# SwitchMultiControl.net
KiCad netlist of a schematic drawn in Altium Designer
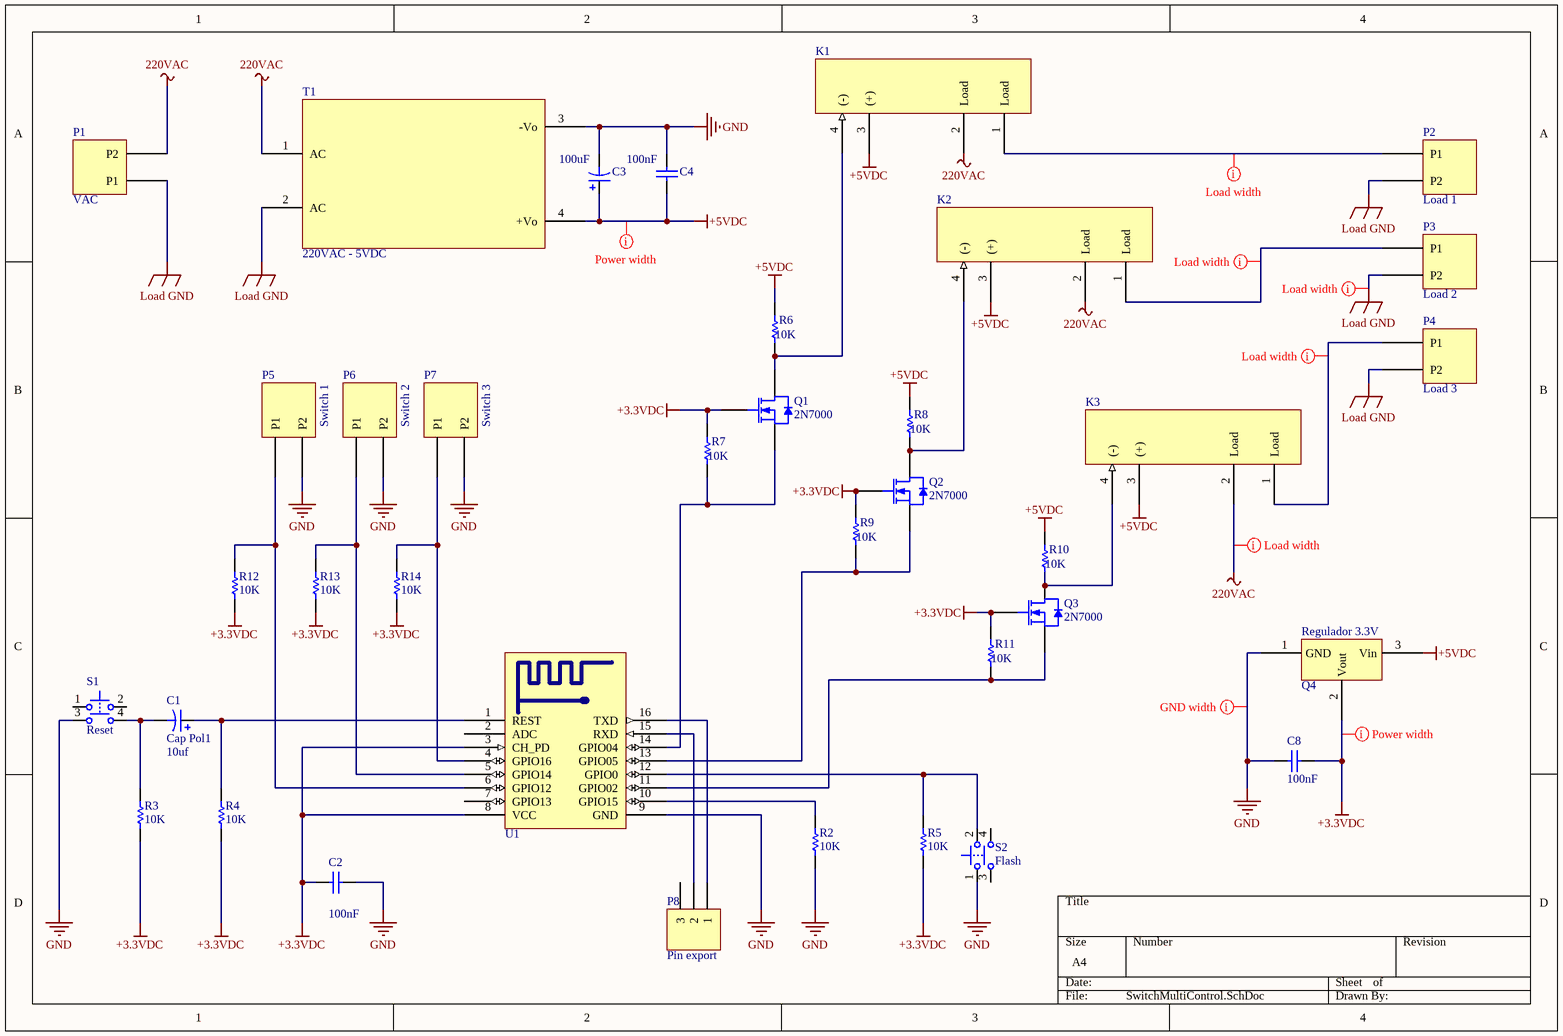
[diagram p0: SwitchMultiControl.SchDoc]

(export (version "E")
  (design (tool "Eeschema 10.0.6"))
  (components
    (comp (ref "C1")
      (value "Cap Pol1")
      (footprint "RAD-0.1")
      (description "Polarized Capacitor (Radial)")
      (fields (field (name "ALTIUM_VALUE") "10uf") (field (name "PUBLISHER") "Altium Limited"))
      (libsource (lib "Miscellaneous Devices") (part "Cap Pol1"))
    )
    (comp (ref "C2")
      (value "100nF")
      (footprint "RAD-0.1")
      (description "Capacitor")
      (fields (field (name "Comment") "Cap") (field (name "PUBLISHER") "Altium Limited"))
      (libsource (lib "Miscellaneous Devices") (part "Cap"))
    )
    (comp (ref "C3")
      (value "100uF")
      (footprint "RAD-0.1")
      (description "Polarized Capacitor (Radial)")
      (fields (field (name "Comment") "Cap Pol1") (field (name "PUBLISHER") "Altium Limited"))
      (libsource (lib "Miscellaneous Devices") (part "Cap Pol1"))
    )
    (comp (ref "C4")
      (value "100nF")
      (footprint "RAD-0.1")
      (description "Capacitor")
      (fields (field (name "Comment") "Cap") (field (name "PUBLISHER") "Altium Limited"))
      (libsource (lib "Miscellaneous Devices") (part "Cap"))
    )
    (comp (ref "C8")
      (value "100nF")
      (footprint "RAD-0.1")
      (description "Capacitor")
      (fields (field (name "Comment") "Cap") (field (name "PUBLISHER") "Altium Limited"))
      (libsource (lib "Miscellaneous Devices") (part "Cap"))
    )
    (comp (ref "K1")
      (value "G3MB-202P DC5")
      (footprint "G3MB-202P DC5")
      (description "RELAY MINI SSR 240VAC@2A ZERO")
      (fields (field (name "MFR") "Omron"))
      (libsource (lib "G3MB-202P") (part "G3MB-202P DC5"))
    )
    (comp (ref "K2")
      (value "G3MB-202P DC5")
      (footprint "G3MB-202P DC5")
      (description "RELAY MINI SSR 240VAC@2A ZERO")
      (fields (field (name "MFR") "Omron"))
      (libsource (lib "G3MB-202P") (part "G3MB-202P DC5"))
    )
    (comp (ref "K3")
      (value "G3MB-202P DC5")
      (footprint "G3MB-202P DC5")
      (description "RELAY MINI SSR 240VAC@2A ZERO")
      (fields (field (name "MFR") "Omron"))
      (libsource (lib "G3MB-202P") (part "G3MB-202P DC5"))
    )
    (comp (ref "P1")
      (value "VAC")
      (footprint "ScrewTerminal-X2")
      (libsource (lib "") (part "ScrewTerminal_1"))
    )
    (comp (ref "P2")
      (value "Load 1")
      (footprint "ScrewTerminal-X2")
      (libsource (lib "ScrewTerminal_2X") (part "ScrewTerminal"))
    )
    (comp (ref "P3")
      (value "Load 2")
      (footprint "ScrewTerminal-X2")
      (libsource (lib "ScrewTerminal_2X") (part "ScrewTerminal"))
    )
    (comp (ref "P4")
      (value "Load 3")
      (footprint "ScrewTerminal-X2")
      (libsource (lib "ScrewTerminal_2X") (part "ScrewTerminal"))
    )
    (comp (ref "P5")
      (value "Switch 1")
      (footprint "ScrewTerminal-X2")
      (libsource (lib "") (part "ScrewTerminal_2"))
    )
    (comp (ref "P6")
      (value "Switch 2")
      (footprint "ScrewTerminal-X2")
      (libsource (lib "") (part "ScrewTerminal_2"))
    )
    (comp (ref "P7")
      (value "Switch 3")
      (footprint "ScrewTerminal-X2")
      (libsource (lib "") (part "ScrewTerminal_2"))
    )
    (comp (ref "P8")
      (value "Pin export")
      (footprint "HDR1X3")
      (description "Header, 3-Pin")
      (fields (field (name "PUBLISHER") "Altium Limited"))
      (libsource (lib "Miscellaneous Connectors") (part "Header 3"))
    )
    (comp (ref "Q1")
      (value "2N7000")
      (footprint "SOT54")
      (description "N-channel Enhancement Mode Field-effect Transistor")
      (fields (field (name "PUBLISHER") "Altium Limited"))
      (libsource (lib "Philips Discrete MOSFET - Low Power") (part "2N7000"))
    )
    (comp (ref "Q2")
      (value "2N7000")
      (footprint "SOT54")
      (description "N-channel Enhancement Mode Field-effect Transistor")
      (fields (field (name "PUBLISHER") "Altium Limited"))
      (libsource (lib "Philips Discrete MOSFET - Low Power") (part "2N7000"))
    )
    (comp (ref "Q3")
      (value "2N7000")
      (footprint "SOT54")
      (description "N-channel Enhancement Mode Field-effect Transistor")
      (fields (field (name "PUBLISHER") "Altium Limited"))
      (libsource (lib "Philips Discrete MOSFET - Low Power") (part "2N7000"))
    )
    (comp (ref "Q4")
      (value "Regulador 3.3V")
      (footprint "TO-220-AB")
      (libsource (lib "AMS1117") (part "AMS1117"))
    )
    (comp (ref "R2")
      (value "10K")
      (footprint "AXIAL-0.3")
      (description "Resistor")
      (fields (field (name "Comment") "Res1") (field (name "PUBLISHER") "Altium Limited"))
      (libsource (lib "Miscellaneous Devices") (part "Res1"))
    )
    (comp (ref "R3")
      (value "10K")
      (footprint "AXIAL-0.3")
      (description "Resistor")
      (fields (field (name "Comment") "Res1") (field (name "PUBLISHER") "Altium Limited"))
      (libsource (lib "Miscellaneous Devices") (part "Res1"))
    )
    (comp (ref "R4")
      (value "10K")
      (footprint "AXIAL-0.3")
      (description "Resistor")
      (fields (field (name "Comment") "Res1") (field (name "PUBLISHER") "Altium Limited"))
      (libsource (lib "Miscellaneous Devices") (part "Res1"))
    )
    (comp (ref "R5")
      (value "10K")
      (footprint "AXIAL-0.3")
      (description "Resistor")
      (fields (field (name "Comment") "Res1") (field (name "PUBLISHER") "Altium Limited"))
      (libsource (lib "Miscellaneous Devices") (part "Res1"))
    )
    (comp (ref "R6")
      (value "10K")
      (footprint "AXIAL-0.3")
      (description "Resistor")
      (fields (field (name "Comment") "Res1") (field (name "PUBLISHER") "Altium Limited"))
      (libsource (lib "Miscellaneous Devices") (part "Res1"))
    )
    (comp (ref "R7")
      (value "10K")
      (footprint "AXIAL-0.3")
      (description "Resistor")
      (fields (field (name "Comment") "Res1") (field (name "PUBLISHER") "Altium Limited"))
      (libsource (lib "Miscellaneous Devices") (part "Res1"))
    )
    (comp (ref "R8")
      (value "10K")
      (footprint "AXIAL-0.3")
      (description "Resistor")
      (fields (field (name "Comment") "Res1") (field (name "PUBLISHER") "Altium Limited"))
      (libsource (lib "Miscellaneous Devices") (part "Res1"))
    )
    (comp (ref "R9")
      (value "10K")
      (footprint "AXIAL-0.3")
      (description "Resistor")
      (fields (field (name "Comment") "Res1") (field (name "PUBLISHER") "Altium Limited"))
      (libsource (lib "Miscellaneous Devices") (part "Res1"))
    )
    (comp (ref "R10")
      (value "10K")
      (footprint "AXIAL-0.3")
      (description "Resistor")
      (fields (field (name "Comment") "Res1") (field (name "PUBLISHER") "Altium Limited"))
      (libsource (lib "Miscellaneous Devices") (part "Res1"))
    )
    (comp (ref "R11")
      (value "10K")
      (footprint "AXIAL-0.3")
      (description "Resistor")
      (fields (field (name "Comment") "Res1") (field (name "PUBLISHER") "Altium Limited"))
      (libsource (lib "Miscellaneous Devices") (part "Res1"))
    )
    (comp (ref "R12")
      (value "10K")
      (footprint "AXIAL-0.3")
      (description "Resistor")
      (fields (field (name "Comment") "Res1") (field (name "PUBLISHER") "Altium Limited"))
      (libsource (lib "Miscellaneous Devices") (part "Res1"))
    )
    (comp (ref "R13")
      (value "10K")
      (footprint "AXIAL-0.3")
      (description "Resistor")
      (fields (field (name "Comment") "Res1") (field (name "PUBLISHER") "Altium Limited"))
      (libsource (lib "Miscellaneous Devices") (part "Res1"))
    )
    (comp (ref "R14")
      (value "10K")
      (footprint "AXIAL-0.3")
      (description "Resistor")
      (fields (field (name "Comment") "Res1") (field (name "PUBLISHER") "Altium Limited"))
      (libsource (lib "Miscellaneous Devices") (part "Res1"))
    )
    (comp (ref "S1")
      (value "Reset")
      (footprint "PushButton")
      (description "Tactile Switch, DPST; Thru-Hole; Vertical; Rating DC 12V, 50mA (max)")
      (fields (field (name "PUBLISHER") "Altium Limited"))
      (libsource (lib "IL Switch Push Button") (part "IT-2175"))
    )
    (comp (ref "S2")
      (value "Flash")
      (footprint "PushButton")
      (description "Tactile Switch, DPST; Thru-Hole; Vertical; Rating DC 12V, 50mA (max)")
      (fields (field (name "PUBLISHER") "Altium Limited"))
      (libsource (lib "IL Switch Push Button") (part "IT-2175"))
    )
    (comp (ref "T1")
      (value "220VAC - 5VDC")
      (footprint "HLK-PM")
      (description "HLK-PM*")
      (fields (field (name "MFR") "HLK-PM01"))
      (libsource (lib "HLK-PM") (part "HLK-PM"))
    )
    (comp (ref "U1") (value "ESP-12") (footprint "ESP_12") (libsource (lib "ESP-12") (part "ESP-12")))
  )
  (nets
    (net (code "1") (name "+3.3VDC") (class "Default")
      (node (ref "C2") (pin "1") (pinfunction "1_1") (pintype "passive"))
      (node (ref "C8") (pin "2") (pinfunction "2_2") (pintype "passive"))
      (node (ref "Q1") (pin "2") (pinfunction "G_2") (pintype "passive"))
      (node (ref "Q2") (pin "2") (pinfunction "G_2") (pintype "passive"))
      (node (ref "Q3") (pin "2") (pinfunction "G_2") (pintype "passive"))
      (node (ref "Q4") (pin "2") (pinfunction "Vout_2") (pintype "passive"))
      (node (ref "R11") (pin "2") (pinfunction "2_2") (pintype "passive"))
      (node (ref "R12") (pin "2") (pinfunction "2_2") (pintype "passive"))
      (node (ref "R13") (pin "2") (pinfunction "2_2") (pintype "passive"))
      (node (ref "R14") (pin "2") (pinfunction "2_2") (pintype "passive"))
      (node (ref "R3") (pin "2") (pinfunction "2_2") (pintype "passive"))
      (node (ref "R4") (pin "2") (pinfunction "2_2") (pintype "passive"))
      (node (ref "R5") (pin "2") (pinfunction "2_2") (pintype "passive"))
      (node (ref "R7") (pin "2") (pinfunction "2_2") (pintype "passive"))
      (node (ref "R9") (pin "2") (pinfunction "2_2") (pintype "passive"))
      (node (ref "U1") (pin "3") (pinfunction "CH_PD_3") (pintype "input"))
      (node (ref "U1") (pin "8") (pinfunction "VCC_8") (pintype "power_in"))
    )
    (net (code "2") (name "+5VDC") (class "Default")
      (node (ref "C3") (pin "1") (pinfunction "1_1") (pintype "passive"))
      (node (ref "C4") (pin "2") (pinfunction "2_2") (pintype "passive"))
      (node (ref "K1") (pin "3") (pinfunction "(+)_3") (pintype "power_in"))
      (node (ref "K2") (pin "3") (pinfunction "(+)_3") (pintype "power_in"))
      (node (ref "K3") (pin "3") (pinfunction "(+)_3") (pintype "power_in"))
      (node (ref "Q4") (pin "3") (pinfunction "Vin_3") (pintype "passive"))
      (node (ref "R10") (pin "2") (pinfunction "2_2") (pintype "passive"))
      (node (ref "R6") (pin "2") (pinfunction "2_2") (pintype "passive"))
      (node (ref "R8") (pin "2") (pinfunction "2_2") (pintype "passive"))
      (node (ref "T1") (pin "4") (pinfunction "+Vo_4") (pintype "passive"))
    )
    (net (code "3") (name "220VAC") (class "Default")
      (node (ref "K1") (pin "2") (pinfunction "Load_2") (pintype "passive"))
      (node (ref "K2") (pin "2") (pinfunction "Load_2") (pintype "passive"))
      (node (ref "K3") (pin "2") (pinfunction "Load_2") (pintype "passive"))
      (node (ref "P1") (pin "2") (pinfunction "P2_2") (pintype "passive"))
      (node (ref "T1") (pin "1") (pinfunction "AC_1") (pintype "power_in"))
    )
    (net (code "4") (name "GND") (class "Default")
      (node (ref "C2") (pin "2") (pinfunction "2_2") (pintype "passive"))
      (node (ref "C3") (pin "2") (pinfunction "2_2") (pintype "passive"))
      (node (ref "C4") (pin "1") (pinfunction "1_1") (pintype "passive"))
      (node (ref "C8") (pin "1") (pinfunction "1_1") (pintype "passive"))
      (node (ref "P5") (pin "2") (pinfunction "P2_2") (pintype "passive"))
      (node (ref "P6") (pin "2") (pinfunction "P2_2") (pintype "passive"))
      (node (ref "P7") (pin "2") (pinfunction "P2_2") (pintype "passive"))
      (node (ref "Q4") (pin "1") (pinfunction "GND_1") (pintype "passive"))
      (node (ref "R2") (pin "2") (pinfunction "2_2") (pintype "passive"))
      (node (ref "S1") (pin "3") (pinfunction "3_3") (pintype "passive"))
      (node (ref "S2") (pin "1") (pinfunction "1_1") (pintype "passive"))
      (node (ref "T1") (pin "3") (pinfunction "-Vo_3") (pintype "passive"))
      (node (ref "U1") (pin "9") (pinfunction "GND_9") (pintype "power_in"))
    )
    (net (code "5") (name "Load GND") (class "Default")
      (node (ref "P1") (pin "1") (pinfunction "P1_1") (pintype "passive"))
      (node (ref "P2") (pin "2") (pinfunction "P2_2") (pintype "passive"))
      (node (ref "P3") (pin "2") (pinfunction "P2_2") (pintype "passive"))
      (node (ref "P4") (pin "2") (pinfunction "P2_2") (pintype "passive"))
      (node (ref "T1") (pin "2") (pinfunction "AC_2") (pintype "power_in"))
    )
    (net (code "6") (name "Net-(C1-Pad2)") (class "Default")
      (node (ref "C1") (pin "2") (pinfunction "2_2") (pintype "passive"))
      (node (ref "R3") (pin "1") (pinfunction "1_1") (pintype "passive"))
      (node (ref "S1") (pin "4") (pinfunction "4_4") (pintype "passive"))
    )
    (net (code "7") (name "Net-(K1-(-))") (class "Default")
      (node (ref "K1") (pin "4") (pinfunction "(-)_4") (pintype "input"))
      (node (ref "Q1") (pin "1") (pinfunction "D_1") (pintype "passive"))
      (node (ref "R6") (pin "1") (pinfunction "1_1") (pintype "passive"))
    )
    (net (code "8") (name "Net-(K2-(-))") (class "Default")
      (node (ref "K2") (pin "4") (pinfunction "(-)_4") (pintype "input"))
      (node (ref "Q2") (pin "1") (pinfunction "D_1") (pintype "passive"))
      (node (ref "R8") (pin "1") (pinfunction "1_1") (pintype "passive"))
    )
    (net (code "9") (name "Net-(K3-(-))") (class "Default")
      (node (ref "K3") (pin "4") (pinfunction "(-)_4") (pintype "input"))
      (node (ref "Q3") (pin "1") (pinfunction "D_1") (pintype "passive"))
      (node (ref "R10") (pin "1") (pinfunction "1_1") (pintype "passive"))
    )
    (net (code "10") (name "Net-(P2-P1)") (class "Default")
      (node (ref "K1") (pin "1") (pinfunction "Load_1") (pintype "passive"))
      (node (ref "P2") (pin "1") (pinfunction "P1_1") (pintype "passive"))
    )
    (net (code "11") (name "Net-(P3-P1)") (class "Default")
      (node (ref "K2") (pin "1") (pinfunction "Load_1") (pintype "passive"))
      (node (ref "P3") (pin "1") (pinfunction "P1_1") (pintype "passive"))
    )
    (net (code "12") (name "Net-(P4-P1)") (class "Default")
      (node (ref "K3") (pin "1") (pinfunction "Load_1") (pintype "passive"))
      (node (ref "P4") (pin "1") (pinfunction "P1_1") (pintype "passive"))
    )
    (net (code "13") (name "Net-(P5-P1)") (class "Default")
      (node (ref "P5") (pin "1") (pinfunction "P1_1") (pintype "passive"))
      (node (ref "R12") (pin "1") (pinfunction "1_1") (pintype "passive"))
      (node (ref "U1") (pin "6") (pinfunction "GPIO12_6") (pintype "bidirectional"))
    )
    (net (code "14") (name "Net-(P6-P1)") (class "Default")
      (node (ref "P6") (pin "1") (pinfunction "P1_1") (pintype "passive"))
      (node (ref "R13") (pin "1") (pinfunction "1_1") (pintype "passive"))
      (node (ref "U1") (pin "5") (pinfunction "GPIO14_5") (pintype "bidirectional"))
    )
    (net (code "15") (name "Net-(P7-P1)") (class "Default")
      (node (ref "P7") (pin "1") (pinfunction "P1_1") (pintype "passive"))
      (node (ref "R14") (pin "1") (pinfunction "1_1") (pintype "passive"))
      (node (ref "U1") (pin "4") (pinfunction "GPIO16_4") (pintype "bidirectional"))
    )
    (net (code "16") (name "Net-(Q1-S)") (class "Default")
      (node (ref "Q1") (pin "3") (pinfunction "S_3") (pintype "passive"))
      (node (ref "R7") (pin "1") (pinfunction "1_1") (pintype "passive"))
      (node (ref "U1") (pin "14") (pinfunction "GPIO04_14") (pintype "bidirectional"))
    )
    (net (code "17") (name "Net-(Q2-S)") (class "Default")
      (node (ref "Q2") (pin "3") (pinfunction "S_3") (pintype "passive"))
      (node (ref "R9") (pin "1") (pinfunction "1_1") (pintype "passive"))
      (node (ref "U1") (pin "13") (pinfunction "GPIO05_13") (pintype "bidirectional"))
    )
    (net (code "18") (name "Net-(Q3-S)") (class "Default")
      (node (ref "Q3") (pin "3") (pinfunction "S_3") (pintype "passive"))
      (node (ref "R11") (pin "1") (pinfunction "1_1") (pintype "passive"))
      (node (ref "U1") (pin "11") (pinfunction "GPIO02_11") (pintype "bidirectional"))
    )
    (net (code "19") (name "Net-(U1-GPIO0)") (class "Default")
      (node (ref "R5") (pin "1") (pinfunction "1_1") (pintype "passive"))
      (node (ref "S2") (pin "2") (pinfunction "2_2") (pintype "passive"))
      (node (ref "U1") (pin "12") (pinfunction "GPIO0_12") (pintype "bidirectional"))
    )
    (net (code "20") (name "Net-(U1-GPIO15)") (class "Default")
      (node (ref "R2") (pin "1") (pinfunction "1_1") (pintype "passive"))
      (node (ref "U1") (pin "10") (pinfunction "GPIO15_10") (pintype "bidirectional"))
    )
    (net (code "21") (name "Net-(U1-REST)") (class "Default")
      (node (ref "C1") (pin "1") (pinfunction "1_1") (pintype "passive"))
      (node (ref "R4") (pin "1") (pinfunction "1_1") (pintype "passive"))
      (node (ref "U1") (pin "1") (pinfunction "REST_1") (pintype "passive"))
    )
    (net (code "22") (name "Net-(U1-RXD)") (class "Default")
      (node (ref "P8") (pin "2") (pinfunction "2_2") (pintype "passive"))
      (node (ref "U1") (pin "15") (pinfunction "RXD_15") (pintype "input"))
    )
    (net (code "23") (name "Net-(U1-TXD)") (class "Default")
      (node (ref "P8") (pin "1") (pinfunction "1_1") (pintype "passive"))
      (node (ref "U1") (pin "16") (pinfunction "TXD_16") (pintype "output"))
    )
    (net (code "24") (name "unconnected-(P8-Pad3)") (class "Default")
      (node (ref "P8") (pin "3") (pinfunction "3_3") (pintype "passive"))
    )
    (net (code "25") (name "unconnected-(S1-Pad1)") (class "Default")
      (node (ref "S1") (pin "1") (pinfunction "1_1") (pintype "passive"))
    )
    (net (code "26") (name "unconnected-(S1-Pad2)") (class "Default")
      (node (ref "S1") (pin "2") (pinfunction "2_2") (pintype "passive"))
    )
    (net (code "27") (name "unconnected-(S2-Pad3)") (class "Default")
      (node (ref "S2") (pin "3") (pinfunction "3_3") (pintype "passive"))
    )
    (net (code "28") (name "unconnected-(S2-Pad4)") (class "Default")
      (node (ref "S2") (pin "4") (pinfunction "4_4") (pintype "passive"))
    )
    (net (code "29") (name "unconnected-(U1-ADC-Pad2)") (class "Default")
      (node (ref "U1") (pin "2") (pinfunction "ADC_2") (pintype "passive"))
    )
    (net (code "30") (name "unconnected-(U1-GPIO13-Pad7)") (class "Default")
      (node (ref "U1") (pin "7") (pinfunction "GPIO13_7") (pintype "bidirectional"))
    )
  )
)
